# OpenBook_Schematic.net
KiCad netlist of a schematic drawn in EAGLE
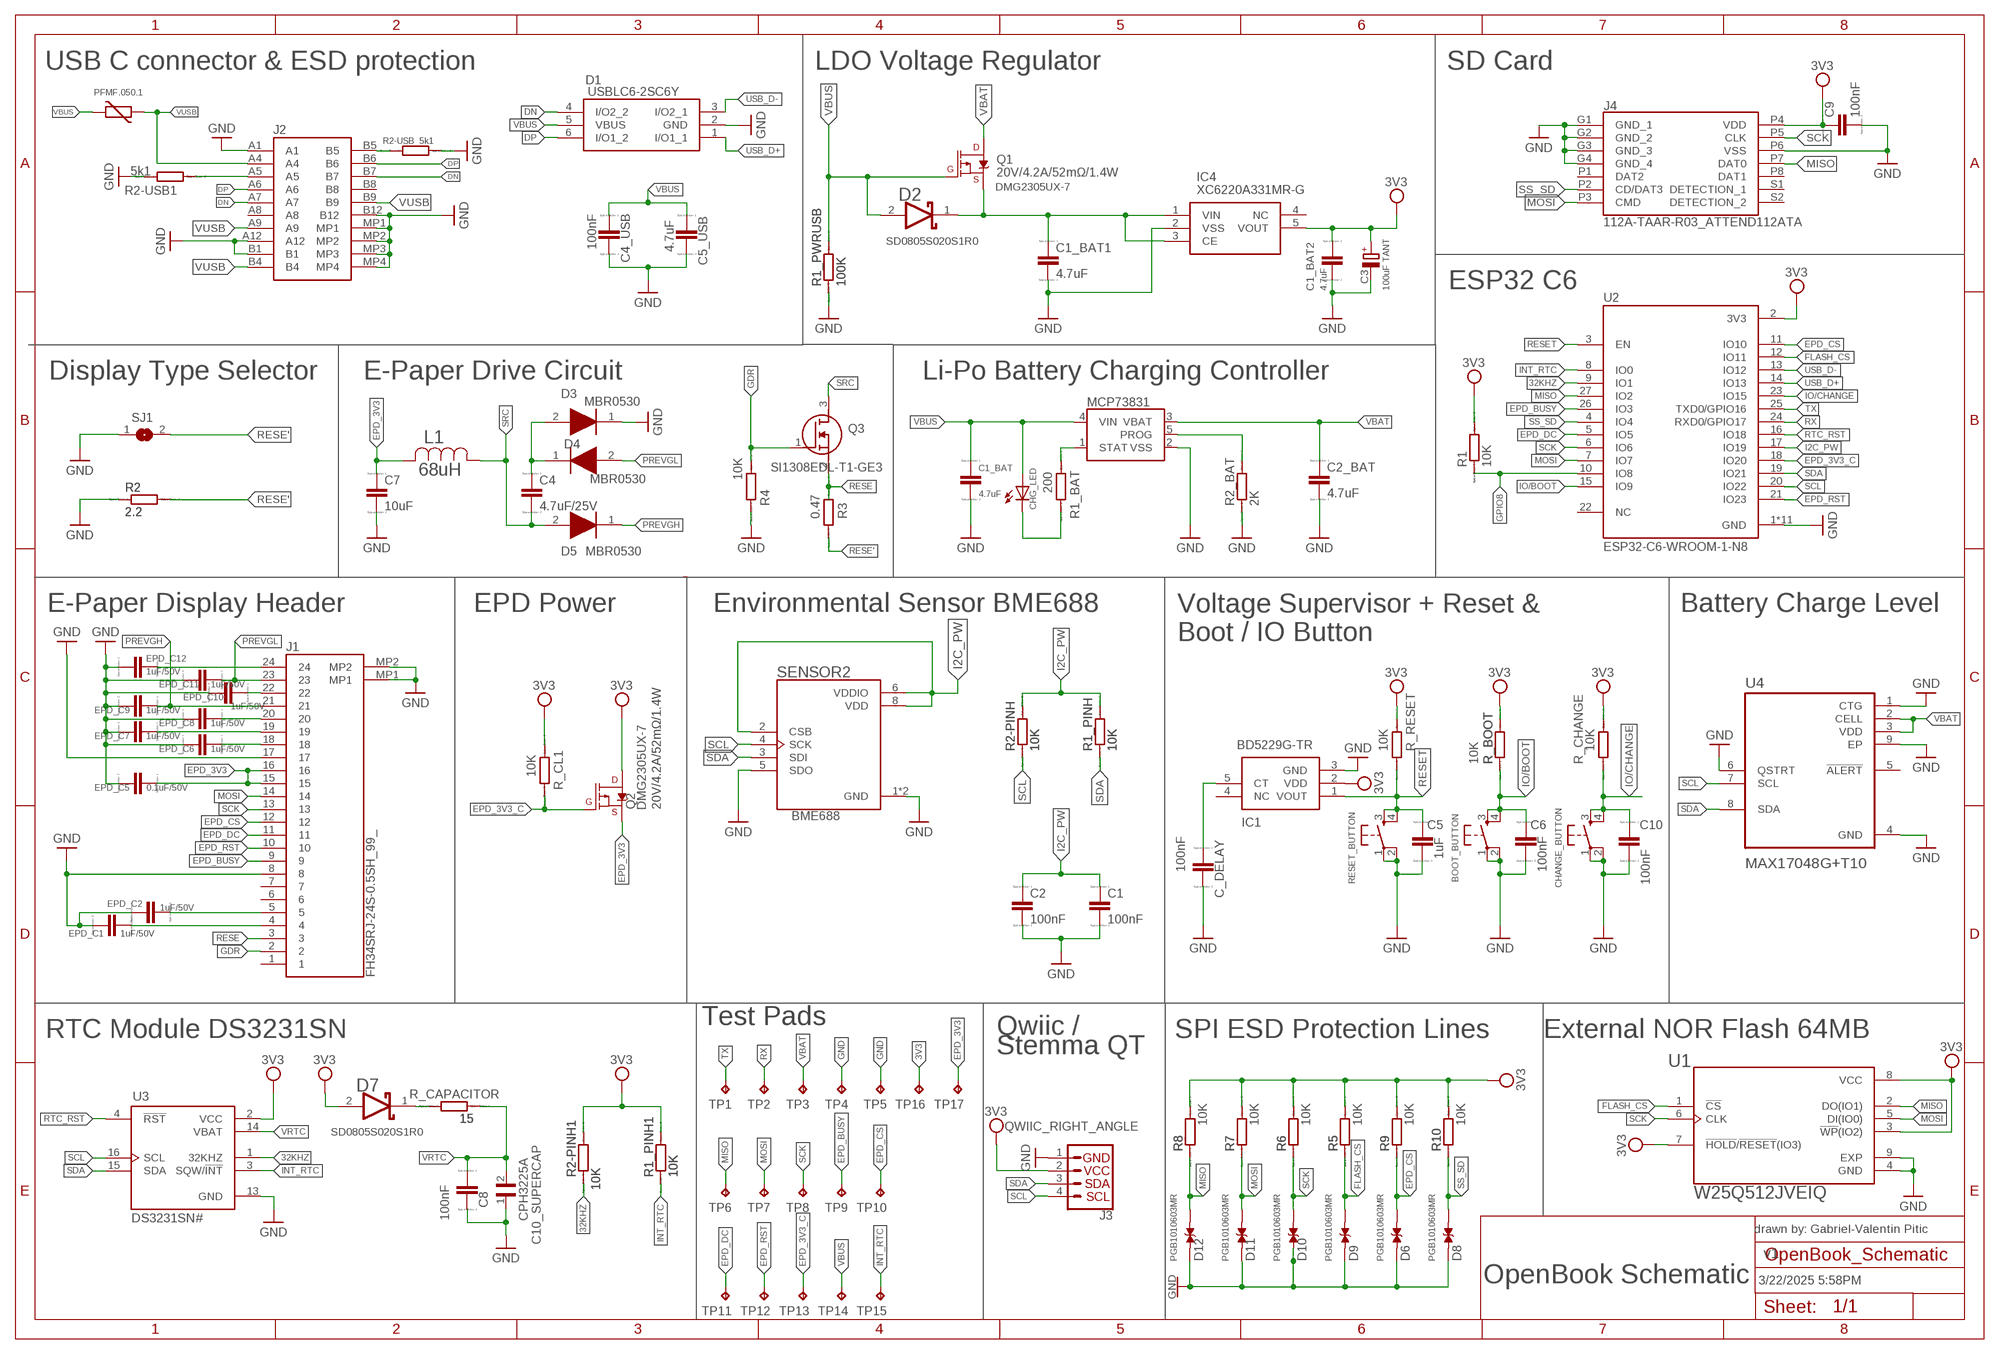
[diagram p0: schematic, sheet 1]

(export (version "E")
  (design (tool "Eeschema 10.0.6"))
  (components
    (comp (ref "BOOT_BUTTON")
      (value "BUTTON_CUSYOMV1")
      (footprint "eagle-import:MYBUTTON")
      (libsource (lib "eagle-import") (part "BUTTON_CUSYOMV1"))
    )
    (comp (ref "C1")
      (value "100nF")
      (footprint "eagle-import:ESP32_WROVER_EAGLE-LTSPICE_C0402")
      (libsource (lib "eagle-import") (part "EAGLE-LTSPICE_CC0402"))
    )
    (comp (ref "C1_BAT")
      (value "4.7uF")
      (footprint "eagle-import:ESP32_WROVER_EAGLE-LTSPICE_C0402")
      (libsource (lib "eagle-import") (part "EAGLE-LTSPICE_CC0402"))
    )
    (comp (ref "C1_BAT1")
      (value "4.7uF")
      (footprint "eagle-import:ESP32_WROVER_EAGLE-LTSPICE_C0402")
      (libsource (lib "eagle-import") (part "EAGLE-LTSPICE_CC0402"))
    )
    (comp (ref "C1_BAT2")
      (value "4.7uF")
      (footprint "eagle-import:ESP32_WROVER_EAGLE-LTSPICE_C0402")
      (libsource (lib "eagle-import") (part "EAGLE-LTSPICE_CC0402"))
    )
    (comp (ref "C2")
      (value "100nF")
      (footprint "eagle-import:ESP32_WROVER_EAGLE-LTSPICE_C0402")
      (libsource (lib "eagle-import") (part "EAGLE-LTSPICE_CC0402"))
    )
    (comp (ref "C2_BAT")
      (value "4.7uF")
      (footprint "eagle-import:ESP32_WROVER_EAGLE-LTSPICE_C0402")
      (libsource (lib "eagle-import") (part "EAGLE-LTSPICE_CC0402"))
    )
    (comp (ref "C3")
      (value "100uF TANT")
      (footprint "eagle-import:RCL_CT3528")
      (libsource (lib "eagle-import") (part "RCL_CPOL-EUCT3528"))
    )
    (comp (ref "C4")
      (value "4.7uF/25V")
      (footprint "eagle-import:ESP32_WROVER_EAGLE-LTSPICE_C0402")
      (libsource (lib "eagle-import") (part "EAGLE-LTSPICE_CC0402"))
    )
    (comp (ref "C4_USB")
      (value "100nF")
      (footprint "eagle-import:ESP32_WROVER_EAGLE-LTSPICE_C0402")
      (libsource (lib "eagle-import") (part "EAGLE-LTSPICE_CC0402"))
    )
    (comp (ref "C5")
      (value "1uF")
      (footprint "eagle-import:ESP32_WROVER_EAGLE-LTSPICE_C0402")
      (libsource (lib "eagle-import") (part "EAGLE-LTSPICE_CC0402"))
    )
    (comp (ref "C5_USB")
      (value "4.7uF")
      (footprint "eagle-import:ESP32_WROVER_EAGLE-LTSPICE_C0402")
      (libsource (lib "eagle-import") (part "EAGLE-LTSPICE_CC0402"))
    )
    (comp (ref "C6")
      (value "100nF")
      (footprint "eagle-import:ESP32_WROVER_EAGLE-LTSPICE_C0402")
      (libsource (lib "eagle-import") (part "EAGLE-LTSPICE_CC0402"))
    )
    (comp (ref "C7")
      (value "10uF")
      (footprint "eagle-import:ESP32_WROVER_EAGLE-LTSPICE_C0402")
      (libsource (lib "eagle-import") (part "EAGLE-LTSPICE_CC0402"))
    )
    (comp (ref "C8")
      (value "100nF")
      (footprint "eagle-import:ESP32_WROVER_EAGLE-LTSPICE_C0402")
      (libsource (lib "eagle-import") (part "EAGLE-LTSPICE_CC0402"))
    )
    (comp (ref "C9")
      (value "100nF")
      (footprint "eagle-import:ESP32_WROVER_EAGLE-LTSPICE_C0402")
      (libsource (lib "eagle-import") (part "EAGLE-LTSPICE_CC0402"))
    )
    (comp (ref "C10")
      (value "100nF")
      (footprint "eagle-import:ESP32_WROVER_EAGLE-LTSPICE_C0402")
      (libsource (lib "eagle-import") (part "EAGLE-LTSPICE_CC0402"))
    )
    (comp (ref "C10_SUPERCAP")
      (value "CPH3225A")
      (footprint "eagle-import:CAPCP3225X100N")
      (fields (field (name "MF") "Seiko Instruments"))
      (libsource (lib "eagle-import") (part "CPH3225A"))
    )
    (comp (ref "CHANGE_BUTTON")
      (value "BUTTON_CUSYOMV1")
      (footprint "eagle-import:MYBUTTON")
      (libsource (lib "eagle-import") (part "BUTTON_CUSYOMV1"))
    )
    (comp (ref "CHG_LED")
      (value "ADAFRUIT_LEDCHIP-LED0603")
      (footprint "eagle-import:ADAFRUIT_CHIP-LED0603")
      (libsource (lib "eagle-import") (part "ADAFRUIT_LEDCHIP-LED0603"))
    )
    (comp (ref "C_DELAY")
      (value "100nF")
      (footprint "eagle-import:ESP32_WROVER_EAGLE-LTSPICE_C0402")
      (libsource (lib "eagle-import") (part "EAGLE-LTSPICE_CC0402"))
    )
    (comp (ref "D1")
      (value "USBLC6-2SC6Y")
      (footprint "eagle-import:SOT95P280X145-6N")
      (fields (field (name "MF") "STMicroelectronics"))
      (libsource (lib "eagle-import") (part "USBLC6-2SC6Y"))
    )
    (comp (ref "D2")
      (value "ESP32_WROVER_AVX---SD0805S020S1R0_AVX_SD0805S020S1R0_0_0AVX_SD0805S020S1R0_0_0")
      (footprint "eagle-import:ESP32_WROVER_AVX---SD0805S020S1R0_AVX_SD0805S020S1R0_0")
      (fields
        (field (name "DIGIKEY_PART_NUMBER") "478-7800-1-ND")
        (field (name "MF") "AVX")
        (field (name "MOUSER_PART_NUMBER") "581-SD0805S020S1R0")
      )
      (libsource (lib "eagle-import") (part "ESP32_WROVER_AVX---SD0805S020S1R0_AVX_SD0805S020S1R0_0_0AVX_SD0805S020S1R0_0_0"))
    )
    (comp (ref "D3")
      (value "MBR0530")
      (footprint "eagle-import:SOD3716X135N")
      (fields (field (name "MF") "ON Semiconductor"))
      (libsource (lib "eagle-import") (part "MBR0530"))
    )
    (comp (ref "D4")
      (value "MBR0530")
      (footprint "eagle-import:SOD3716X135N")
      (fields (field (name "MF") "ON Semiconductor"))
      (libsource (lib "eagle-import") (part "MBR0530"))
    )
    (comp (ref "D5")
      (value "MBR0530")
      (footprint "eagle-import:SOD3716X135N")
      (fields (field (name "MF") "ON Semiconductor"))
      (libsource (lib "eagle-import") (part "MBR0530"))
    )
    (comp (ref "D6")
      (value "PGB1010603MR")
      (footprint "eagle-import:DIOC1608X36N")
      (fields (field (name "MF") "Littelfuse Inc."))
      (libsource (lib "eagle-import") (part "PGB1010603MR"))
    )
    (comp (ref "D7")
      (value "ESP32_WROVER_AVX---SD0805S020S1R0_AVX_SD0805S020S1R0_0_0AVX_SD0805S020S1R0_0_0")
      (footprint "eagle-import:ESP32_WROVER_AVX---SD0805S020S1R0_AVX_SD0805S020S1R0_0")
      (fields
        (field (name "DIGIKEY_PART_NUMBER") "478-7800-1-ND")
        (field (name "MF") "AVX")
        (field (name "MOUSER_PART_NUMBER") "581-SD0805S020S1R0")
      )
      (libsource (lib "eagle-import") (part "ESP32_WROVER_AVX---SD0805S020S1R0_AVX_SD0805S020S1R0_0_0AVX_SD0805S020S1R0_0_0"))
    )
    (comp (ref "D8")
      (value "PGB1010603MR")
      (footprint "eagle-import:DIOC1608X36N")
      (fields (field (name "MF") "Littelfuse Inc."))
      (libsource (lib "eagle-import") (part "PGB1010603MR"))
    )
    (comp (ref "D9")
      (value "PGB1010603MR")
      (footprint "eagle-import:DIOC1608X36N")
      (fields (field (name "MF") "Littelfuse Inc."))
      (libsource (lib "eagle-import") (part "PGB1010603MR"))
    )
    (comp (ref "D10")
      (value "PGB1010603MR")
      (footprint "eagle-import:DIOC1608X36N")
      (fields (field (name "MF") "Littelfuse Inc."))
      (libsource (lib "eagle-import") (part "PGB1010603MR"))
    )
    (comp (ref "D11")
      (value "PGB1010603MR")
      (footprint "eagle-import:DIOC1608X36N")
      (fields (field (name "MF") "Littelfuse Inc."))
      (libsource (lib "eagle-import") (part "PGB1010603MR"))
    )
    (comp (ref "D12")
      (value "PGB1010603MR")
      (footprint "eagle-import:DIOC1608X36N")
      (fields (field (name "MF") "Littelfuse Inc."))
      (libsource (lib "eagle-import") (part "PGB1010603MR"))
    )
    (comp (ref "EPD_C1")
      (value "1uF/50V")
      (footprint "eagle-import:ESP32_WROVER_EAGLE-LTSPICE_C0402")
      (libsource (lib "eagle-import") (part "EAGLE-LTSPICE_CC0402"))
    )
    (comp (ref "EPD_C2")
      (value "1uF/50V")
      (footprint "eagle-import:ESP32_WROVER_EAGLE-LTSPICE_C0402")
      (libsource (lib "eagle-import") (part "EAGLE-LTSPICE_CC0402"))
    )
    (comp (ref "EPD_C5")
      (value "0.1uF/50V")
      (footprint "eagle-import:ESP32_WROVER_EAGLE-LTSPICE_C0402")
      (libsource (lib "eagle-import") (part "EAGLE-LTSPICE_CC0402"))
    )
    (comp (ref "EPD_C6")
      (value "1uF/50V")
      (footprint "eagle-import:ESP32_WROVER_EAGLE-LTSPICE_C0402")
      (libsource (lib "eagle-import") (part "EAGLE-LTSPICE_CC0402"))
    )
    (comp (ref "EPD_C7")
      (value "1uF/50V")
      (footprint "eagle-import:ESP32_WROVER_EAGLE-LTSPICE_C0402")
      (libsource (lib "eagle-import") (part "EAGLE-LTSPICE_CC0402"))
    )
    (comp (ref "EPD_C8")
      (value "1uF/50V")
      (footprint "eagle-import:ESP32_WROVER_EAGLE-LTSPICE_C0402")
      (libsource (lib "eagle-import") (part "EAGLE-LTSPICE_CC0402"))
    )
    (comp (ref "EPD_C9")
      (value "1uF/50V")
      (footprint "eagle-import:ESP32_WROVER_EAGLE-LTSPICE_C0402")
      (libsource (lib "eagle-import") (part "EAGLE-LTSPICE_CC0402"))
    )
    (comp (ref "EPD_C10")
      (value "1uF/50V")
      (footprint "eagle-import:ESP32_WROVER_EAGLE-LTSPICE_C0402")
      (libsource (lib "eagle-import") (part "EAGLE-LTSPICE_CC0402"))
    )
    (comp (ref "EPD_C11")
      (value "1uF/50V")
      (footprint "eagle-import:ESP32_WROVER_EAGLE-LTSPICE_C0402")
      (libsource (lib "eagle-import") (part "EAGLE-LTSPICE_CC0402"))
    )
    (comp (ref "EPD_C12")
      (value "1uF/50V")
      (footprint "eagle-import:ESP32_WROVER_EAGLE-LTSPICE_C0402")
      (libsource (lib "eagle-import") (part "EAGLE-LTSPICE_CC0402"))
    )
    (comp (ref "IC1")
      (value "BD5229G-TR")
      (footprint "eagle-import:SOT95P280X125-5N")
      (fields (field (name "MOUSER_PART_NUMBER") "755-BD5229G-TR"))
      (libsource (lib "eagle-import") (part "BD5229G-TR"))
    )
    (comp (ref "IC4")
      (value "XC6220A331MR-G")
      (footprint "eagle-import:SOT95P280X120-5N")
      (fields (field (name "MOUSER_PART_NUMBER") "865-XC6220A331MR-G"))
      (libsource (lib "eagle-import") (part "XC6220A331MR-G"))
    )
    (comp (ref "J1")
      (value "FH34SRJ-24S-0.5SH_99_")
      (footprint "eagle-import:FH34SRJ24S05SH99")
      (fields
        (field (name "MANUFACTURER_PART_NUMBER") "FH34SRJ-24S-0.5SH(99)")
        (field (name "MOUSER_PART_NUMBER") "798-FH34SRJ24S05SH99")
      )
      (libsource (lib "eagle-import") (part "FH34SRJ-24S-0.5SH_99_"))
    )
    (comp (ref "J2")
      (value "SAMACSYS_PARTS_USB4110-GF-A")
      (footprint "eagle-import:SAMACSYS_PARTS_USB4110GFA")
      (libsource (lib "eagle-import") (part "SAMACSYS_PARTS_USB4110-GF-A"))
    )
    (comp (ref "J3")
      (value "QWIIC_RIGHT_ANGLE")
      (footprint "eagle-import:JST04_1MM_RA")
      (libsource (lib "eagle-import") (part "QWIIC_CONNECTORJS-1MM"))
    )
    (comp (ref "J4")
      (value "112A-TAAR-R03_ATTEND112ATA")
      (footprint "eagle-import:112ATAARR03ATTEND")
      (libsource (lib "eagle-import") (part "112A-TAAR-R03_ATTEND112ATA"))
    )
    (comp (ref "L1")
      (value "68uH")
      (footprint "eagle-import:IND_4828-WE-TPC_WRE")
      (fields
        (field (name "MANUFACTURER_PART_NUMBER") "744043680")
        (field (name "COPYRIGHT") "Copyright (C) 2024 Ultra Librarian. All rights reserved.")
      )
      (libsource (lib "eagle-import") (part "744043680IND_4828-WE-TPC_WRE"))
    )
    (comp (ref "MCP73831")
      (value "ESP32_WROVER_SPARKFUN-IC-POWER_MCP73831")
      (footprint "eagle-import:ESP32_WROVER_SPARKFUN-IC-POWER_SOT23-5")
      (libsource (lib "eagle-import") (part "ESP32_WROVER_SPARKFUN-IC-POWER_MCP73831"))
    )
    (comp (ref "PFMF.050.1")
      (value "ESP32C6_VARISTOR")
      (footprint "eagle-import:ESP32C6_VARISTOR_CT_CN1812")
      (libsource (lib "eagle-import") (part "ESP32C6_VARISTOR"))
    )
    (comp (ref "Q1")
      (value "20V/4.2A/52mΩ/1.4W")
      (footprint "eagle-import:ESP32_WROVER_SPARKFUN-DISCRETESEMI_SOT23-3")
      (libsource (lib "eagle-import") (part "ESP32_WROVER_SPARKFUN-DISCRETESEMI_MOSFET_PCH-DMG2305UX-7"))
    )
    (comp (ref "Q2")
      (value "20V/4.2A/52mΩ/1.4W")
      (footprint "eagle-import:ESP32_WROVER_SPARKFUN-DISCRETESEMI_SOT23-3")
      (libsource (lib "eagle-import") (part "ESP32_WROVER_SPARKFUN-DISCRETESEMI_MOSFET_PCH-DMG2305UX-7"))
    )
    (comp (ref "Q3")
      (value "SI1308EDL-T1-GE3")
      (footprint "eagle-import:SOT65P210X110-3N")
      (fields (field (name "MF") "Vishay Siliconix"))
      (libsource (lib "eagle-import") (part "SI1308EDL-T1-GE3"))
    )
    (comp (ref "R1")
      (value "10K")
      (footprint "eagle-import:ESP32_WROVER_EAGLE-LTSPICE_R0402")
      (libsource (lib "eagle-import") (part "ESP32_WROVER_EAGLE-LTSPICE_RR0402"))
    )
    (comp (ref "R1_BAT")
      (value "200")
      (footprint "eagle-import:ESP32_WROVER_EAGLE-LTSPICE_R0402")
      (libsource (lib "eagle-import") (part "ESP32_WROVER_EAGLE-LTSPICE_RR0402"))
    )
    (comp (ref "R1_PINH")
      (value "10K")
      (footprint "eagle-import:ESP32_WROVER_EAGLE-LTSPICE_R0402")
      (libsource (lib "eagle-import") (part "ESP32_WROVER_EAGLE-LTSPICE_RR0402"))
    )
    (comp (ref "R1_PINH1")
      (value "10K")
      (footprint "eagle-import:ESP32_WROVER_EAGLE-LTSPICE_R0402")
      (libsource (lib "eagle-import") (part "ESP32_WROVER_EAGLE-LTSPICE_RR0402"))
    )
    (comp (ref "R1_PWRUSB")
      (value "100K")
      (footprint "eagle-import:ESP32_WROVER_EAGLE-LTSPICE_R0402")
      (libsource (lib "eagle-import") (part "ESP32_WROVER_EAGLE-LTSPICE_RR0402"))
    )
    (comp (ref "R2")
      (value "2.2")
      (footprint "eagle-import:ESP32_WROVER_EAGLE-LTSPICE_R0402")
      (libsource (lib "eagle-import") (part "ESP32_WROVER_EAGLE-LTSPICE_RR0402"))
    )
    (comp (ref "R2-PINH")
      (value "10K")
      (footprint "eagle-import:ESP32_WROVER_EAGLE-LTSPICE_R0402")
      (libsource (lib "eagle-import") (part "ESP32_WROVER_EAGLE-LTSPICE_RR0402"))
    )
    (comp (ref "R2-PINH1")
      (value "10K")
      (footprint "eagle-import:ESP32_WROVER_EAGLE-LTSPICE_R0402")
      (libsource (lib "eagle-import") (part "ESP32_WROVER_EAGLE-LTSPICE_RR0402"))
    )
    (comp (ref "R2-USB")
      (value "5k1")
      (footprint "eagle-import:ESP32_WROVER_EAGLE-LTSPICE_R0402")
      (libsource (lib "eagle-import") (part "ESP32_WROVER_EAGLE-LTSPICE_RR0402"))
    )
    (comp (ref "R2-USB1")
      (value "5k1")
      (footprint "eagle-import:ESP32_WROVER_EAGLE-LTSPICE_R0402")
      (libsource (lib "eagle-import") (part "ESP32_WROVER_EAGLE-LTSPICE_RR0402"))
    )
    (comp (ref "R2_BAT")
      (value "2K")
      (footprint "eagle-import:ESP32_WROVER_EAGLE-LTSPICE_R0402")
      (libsource (lib "eagle-import") (part "ESP32_WROVER_EAGLE-LTSPICE_RR0402"))
    )
    (comp (ref "R3")
      (value "0.47")
      (footprint "eagle-import:ESP32_WROVER_EAGLE-LTSPICE_R0402")
      (libsource (lib "eagle-import") (part "ESP32_WROVER_EAGLE-LTSPICE_RR0402"))
    )
    (comp (ref "R4")
      (value "10K")
      (footprint "eagle-import:ESP32_WROVER_EAGLE-LTSPICE_R0402")
      (libsource (lib "eagle-import") (part "ESP32_WROVER_EAGLE-LTSPICE_RR0402"))
    )
    (comp (ref "R5")
      (value "10K")
      (footprint "eagle-import:ESP32_WROVER_EAGLE-LTSPICE_R0402")
      (libsource (lib "eagle-import") (part "ESP32_WROVER_EAGLE-LTSPICE_RR0402"))
    )
    (comp (ref "R6")
      (value "10K")
      (footprint "eagle-import:ESP32_WROVER_EAGLE-LTSPICE_R0402")
      (libsource (lib "eagle-import") (part "ESP32_WROVER_EAGLE-LTSPICE_RR0402"))
    )
    (comp (ref "R7")
      (value "10K")
      (footprint "eagle-import:ESP32_WROVER_EAGLE-LTSPICE_R0402")
      (libsource (lib "eagle-import") (part "ESP32_WROVER_EAGLE-LTSPICE_RR0402"))
    )
    (comp (ref "R8")
      (value "10K")
      (footprint "eagle-import:ESP32_WROVER_EAGLE-LTSPICE_R0402")
      (libsource (lib "eagle-import") (part "ESP32_WROVER_EAGLE-LTSPICE_RR0402"))
    )
    (comp (ref "R9")
      (value "10K")
      (footprint "eagle-import:ESP32_WROVER_EAGLE-LTSPICE_R0402")
      (libsource (lib "eagle-import") (part "ESP32_WROVER_EAGLE-LTSPICE_RR0402"))
    )
    (comp (ref "R10")
      (value "10K")
      (footprint "eagle-import:ESP32_WROVER_EAGLE-LTSPICE_R0402")
      (libsource (lib "eagle-import") (part "ESP32_WROVER_EAGLE-LTSPICE_RR0402"))
    )
    (comp (ref "RESET_BUTTON")
      (value "BUTTON_CUSYOMV1")
      (footprint "eagle-import:MYBUTTON")
      (libsource (lib "eagle-import") (part "BUTTON_CUSYOMV1"))
    )
    (comp (ref "R_BOOT")
      (value "10K")
      (footprint "eagle-import:ESP32_WROVER_EAGLE-LTSPICE_R0402")
      (libsource (lib "eagle-import") (part "ESP32_WROVER_EAGLE-LTSPICE_RR0402"))
    )
    (comp (ref "R_CAPACITOR")
      (value "15")
      (footprint "eagle-import:ESP32_WROVER_EAGLE-LTSPICE_R0402")
      (libsource (lib "eagle-import") (part "ESP32_WROVER_EAGLE-LTSPICE_RR0402"))
    )
    (comp (ref "R_CHANGE")
      (value "10K")
      (footprint "eagle-import:ESP32_WROVER_EAGLE-LTSPICE_R0402")
      (libsource (lib "eagle-import") (part "ESP32_WROVER_EAGLE-LTSPICE_RR0402"))
    )
    (comp (ref "R_CL1")
      (value "10K")
      (footprint "eagle-import:ESP32_WROVER_EAGLE-LTSPICE_R0402")
      (libsource (lib "eagle-import") (part "ESP32_WROVER_EAGLE-LTSPICE_RR0402"))
    )
    (comp (ref "R_RESET")
      (value "10K")
      (footprint "eagle-import:ESP32_WROVER_EAGLE-LTSPICE_R0402")
      (libsource (lib "eagle-import") (part "ESP32_WROVER_EAGLE-LTSPICE_RR0402"))
    )
    (comp (ref "SENSOR2")
      (value "ESP32_WROVER_BME680_BME680")
      (footprint "eagle-import:ESP32_WROVER_BME680_PSON80P300X300X100-8N")
      (fields (field (name "MF") "Bosch Sensortec") (field (name "MP") "BME680"))
      (libsource (lib "eagle-import") (part "ESP32_WROVER_BME680_BME680"))
    )
    (comp (ref "SJ1") (value "SJ") (footprint "eagle-import:SJ") (libsource (lib "eagle-import") (part "SJ")))
    (comp (ref "TP1")
      (value "TPTP20R")
      (footprint "eagle-import:TP20R")
      (libsource (lib "eagle-import") (part "TPTP20R"))
    )
    (comp (ref "TP2")
      (value "TPTP20R")
      (footprint "eagle-import:TP20R")
      (libsource (lib "eagle-import") (part "TPTP20R"))
    )
    (comp (ref "TP3")
      (value "TPTP20R")
      (footprint "eagle-import:TP20R")
      (libsource (lib "eagle-import") (part "TPTP20R"))
    )
    (comp (ref "TP4")
      (value "TPTP20R")
      (footprint "eagle-import:TP20R")
      (libsource (lib "eagle-import") (part "TPTP20R"))
    )
    (comp (ref "TP5")
      (value "TPTP20R")
      (footprint "eagle-import:TP20R")
      (libsource (lib "eagle-import") (part "TPTP20R"))
    )
    (comp (ref "TP6")
      (value "TPTP20R")
      (footprint "eagle-import:TP20R")
      (libsource (lib "eagle-import") (part "TPTP20R"))
    )
    (comp (ref "TP7")
      (value "TPTP20R")
      (footprint "eagle-import:TP20R")
      (libsource (lib "eagle-import") (part "TPTP20R"))
    )
    (comp (ref "TP8")
      (value "TPTP20R")
      (footprint "eagle-import:TP20R")
      (libsource (lib "eagle-import") (part "TPTP20R"))
    )
    (comp (ref "TP9")
      (value "TPTP20R")
      (footprint "eagle-import:TP20R")
      (libsource (lib "eagle-import") (part "TPTP20R"))
    )
    (comp (ref "TP10")
      (value "TPTP20R")
      (footprint "eagle-import:TP20R")
      (libsource (lib "eagle-import") (part "TPTP20R"))
    )
    (comp (ref "TP11")
      (value "TPTP20R")
      (footprint "eagle-import:TP20R")
      (libsource (lib "eagle-import") (part "TPTP20R"))
    )
    (comp (ref "TP12")
      (value "TPTP20R")
      (footprint "eagle-import:TP20R")
      (libsource (lib "eagle-import") (part "TPTP20R"))
    )
    (comp (ref "TP13")
      (value "TPTP20R")
      (footprint "eagle-import:TP20R")
      (libsource (lib "eagle-import") (part "TPTP20R"))
    )
    (comp (ref "TP14")
      (value "TPTP20R")
      (footprint "eagle-import:TP20R")
      (libsource (lib "eagle-import") (part "TPTP20R"))
    )
    (comp (ref "TP15")
      (value "TPTP20R")
      (footprint "eagle-import:TP20R")
      (libsource (lib "eagle-import") (part "TPTP20R"))
    )
    (comp (ref "TP16")
      (value "TPTP20R")
      (footprint "eagle-import:TP20R")
      (libsource (lib "eagle-import") (part "TPTP20R"))
    )
    (comp (ref "TP17")
      (value "TPTP20R")
      (footprint "eagle-import:TP20R")
      (libsource (lib "eagle-import") (part "TPTP20R"))
    )
    (comp (ref "U1")
      (value "W25Q512JVEIQ")
      (footprint "eagle-import:SON50P200X200X80-9N")
      (fields (field (name "MF") "Winbond Electronics"))
      (libsource (lib "eagle-import") (part "W25Q512JVEIQ"))
    )
    (comp (ref "U2")
      (value "ESP32-C6-WROOM-1-N8")
      (footprint "eagle-import:ESP32-C6-WROOM-1-N8")
      (libsource (lib "eagle-import") (part "ESP32-C6-WROOM-1-N8"))
    )
    (comp (ref "U3")
      (value "DS3231SN#")
      (footprint "eagle-import:SOIC127P1032X265-16N")
      (fields (field (name "MF") "Analog Devices"))
      (libsource (lib "eagle-import") (part "DS3231SN#"))
    )
    (comp (ref "U4")
      (value "MAX17048G+T10")
      (footprint "eagle-import:SON50P200X200X80-9N")
      (fields (field (name "MF") "Analog Devices"))
      (libsource (lib "eagle-import") (part "MAX17048G+T10"))
    )
  )
  (nets
    (net (code "1") (name "/CHG_STATUS") (class "Default")
      (node (ref "CHG_LED") (pin "C") (pinfunction "C_C") (pintype "passive"))
      (node (ref "MCP73831") (pin "1") (pinfunction "STAT_1") (pintype "output"))
      (node (ref "R1_BAT") (pin "1") (pinfunction "1_1") (pintype "passive"))
      (node (ref "R1_BAT") (pin "2") (pinfunction "2_2") (pintype "passive"))
    )
    (net (code "2") (name "3V3") (class "Default")
      (node (ref "C1_BAT2") (pin "1") (pinfunction "1_1") (pintype "passive"))
      (node (ref "C3") (pin "+") (pinfunction "+_+") (pintype "passive"))
      (node (ref "C9") (pin "1") (pinfunction "1_1") (pintype "passive"))
      (node (ref "D7") (pin "2") (pinfunction "ANODE_2") (pintype "bidirectional"))
      (node (ref "IC1") (pin "2") (pinfunction "VDD_2") (pintype "bidirectional"))
      (node (ref "IC4") (pin "5") (pinfunction "VOUT_5") (pintype "bidirectional"))
      (node (ref "J3") (pin "2") (pinfunction "2_2") (pintype "power_in"))
      (node (ref "J4") (pin "P4") (pinfunction "VDD_P4") (pintype "bidirectional"))
      (node (ref "Q2") (pin "3") (pinfunction "D_3") (pintype "bidirectional"))
      (node (ref "R1") (pin "2") (pinfunction "2_2") (pintype "passive"))
      (node (ref "R10") (pin "2") (pinfunction "2_2") (pintype "passive"))
      (node (ref "R1_PINH1") (pin "2") (pinfunction "2_2") (pintype "passive"))
      (node (ref "R2-PINH1") (pin "2") (pinfunction "2_2") (pintype "passive"))
      (node (ref "R5") (pin "2") (pinfunction "2_2") (pintype "passive"))
      (node (ref "R6") (pin "2") (pinfunction "2_2") (pintype "passive"))
      (node (ref "R7") (pin "2") (pinfunction "2_2") (pintype "passive"))
      (node (ref "R8") (pin "2") (pinfunction "2_2") (pintype "passive"))
      (node (ref "R9") (pin "2") (pinfunction "2_2") (pintype "passive"))
      (node (ref "R_BOOT") (pin "2") (pinfunction "2_2") (pintype "passive"))
      (node (ref "R_CHANGE") (pin "2") (pinfunction "2_2") (pintype "passive"))
      (node (ref "R_CL1") (pin "2") (pinfunction "2_2") (pintype "passive"))
      (node (ref "R_RESET") (pin "2") (pinfunction "2_2") (pintype "passive"))
      (node (ref "TP16") (pin "TP") (pinfunction "TP_TP") (pintype "input"))
      (node (ref "U1") (pin "3") (pinfunction "~{WP}(IO2)_3") (pintype "bidirectional"))
      (node (ref "U1") (pin "7") (pinfunction "~{HOLD}/~{RESET}(IO3)_7") (pintype "bidirectional"))
      (node (ref "U1") (pin "8") (pinfunction "VCC_8") (pintype "power_in"))
      (node (ref "U2") (pin "2") (pinfunction "3V3_2") (pintype "power_in"))
      (node (ref "U3") (pin "2") (pinfunction "VCC_2") (pintype "power_in"))
    )
    (net (code "3") (name "32KHZ") (class "Default")
      (node (ref "R2-PINH1") (pin "1") (pinfunction "1_1") (pintype "passive"))
      (node (ref "U2") (pin "9") (pinfunction "IO1_9") (pintype "bidirectional"))
      (node (ref "U3") (pin "1") (pinfunction "32KHZ_1") (pintype "output"))
    )
    (net (code "4") (name "DN") (class "Default")
      (node (ref "D1") (pin "4") (pinfunction "I/O2_2_4") (pintype "bidirectional"))
      (node (ref "J2") (pin "A7") (pinfunction "A7_A7") (pintype "bidirectional"))
      (node (ref "J2") (pin "B7") (pinfunction "B7_B7") (pintype "bidirectional"))
    )
    (net (code "5") (name "DP") (class "Default")
      (node (ref "D1") (pin "6") (pinfunction "I/O1_2_6") (pintype "bidirectional"))
      (node (ref "J2") (pin "A6") (pinfunction "A6_A6") (pintype "bidirectional"))
      (node (ref "J2") (pin "B6") (pinfunction "B6_B6") (pintype "bidirectional"))
    )
    (net (code "6") (name "EPD_3V3") (class "Default")
      (node (ref "C7") (pin "1") (pinfunction "1_1") (pintype "passive"))
      (node (ref "EPD_C5") (pin "1") (pinfunction "1_1") (pintype "passive"))
      (node (ref "J1") (pin "15") (pinfunction "15_15") (pintype "bidirectional"))
      (node (ref "J1") (pin "16") (pinfunction "16_16") (pintype "bidirectional"))
      (node (ref "L1") (pin "2") (pinfunction "2_2") (pintype "passive"))
      (node (ref "Q2") (pin "2") (pinfunction "S_2") (pintype "bidirectional"))
      (node (ref "TP17") (pin "TP") (pinfunction "TP_TP") (pintype "input"))
    )
    (net (code "7") (name "EPD_3V3_C") (class "Default")
      (node (ref "Q2") (pin "1") (pinfunction "G_1") (pintype "bidirectional"))
      (node (ref "R_CL1") (pin "1") (pinfunction "1_1") (pintype "passive"))
      (node (ref "TP13") (pin "TP") (pinfunction "TP_TP") (pintype "input"))
      (node (ref "U2") (pin "18") (pinfunction "IO20_18") (pintype "bidirectional"))
    )
    (net (code "8") (name "EPD_BUSY") (class "Default")
      (node (ref "J1") (pin "9") (pinfunction "9_9") (pintype "bidirectional"))
      (node (ref "TP9") (pin "TP") (pinfunction "TP_TP") (pintype "input"))
      (node (ref "U2") (pin "26") (pinfunction "IO3_26") (pintype "bidirectional"))
    )
    (net (code "9") (name "EPD_CS") (class "Default")
      (node (ref "D6") (pin "2") (pinfunction "2_2") (pintype "passive"))
      (node (ref "J1") (pin "12") (pinfunction "12_12") (pintype "bidirectional"))
      (node (ref "R9") (pin "1") (pinfunction "1_1") (pintype "passive"))
      (node (ref "TP10") (pin "TP") (pinfunction "TP_TP") (pintype "input"))
      (node (ref "U2") (pin "11") (pinfunction "IO10_11") (pintype "bidirectional"))
    )
    (net (code "10") (name "EPD_DC") (class "Default")
      (node (ref "J1") (pin "11") (pinfunction "11_11") (pintype "bidirectional"))
      (node (ref "TP11") (pin "TP") (pinfunction "TP_TP") (pintype "input"))
      (node (ref "U2") (pin "5") (pinfunction "IO5_5") (pintype "bidirectional"))
    )
    (net (code "11") (name "EPD_RST") (class "Default")
      (node (ref "J1") (pin "10") (pinfunction "10_10") (pintype "bidirectional"))
      (node (ref "TP12") (pin "TP") (pinfunction "TP_TP") (pintype "input"))
      (node (ref "U2") (pin "21") (pinfunction "IO23_21") (pintype "bidirectional"))
    )
    (net (code "12") (name "FLASH_CS") (class "Default")
      (node (ref "D9") (pin "2") (pinfunction "2_2") (pintype "passive"))
      (node (ref "R5") (pin "1") (pinfunction "1_1") (pintype "passive"))
      (node (ref "U1") (pin "1") (pinfunction "~{CS}_1") (pintype "input"))
      (node (ref "U2") (pin "12") (pinfunction "IO11_12") (pintype "bidirectional"))
    )
    (net (code "13") (name "GDR") (class "Default")
      (node (ref "J1") (pin "2") (pinfunction "2_2") (pintype "bidirectional"))
      (node (ref "Q3") (pin "1") (pinfunction "G_1") (pintype "bidirectional"))
      (node (ref "R4") (pin "2") (pinfunction "2_2") (pintype "passive"))
    )
    (net (code "14") (name "GND") (class "Default")
      (node (ref "BOOT_BUTTON") (pin "1") (pinfunction "1_1") (pintype "passive"))
      (node (ref "BOOT_BUTTON") (pin "2") (pinfunction "2_2") (pintype "passive"))
      (node (ref "C1") (pin "2") (pinfunction "2_2") (pintype "passive"))
      (node (ref "C10") (pin "2") (pinfunction "2_2") (pintype "passive"))
      (node (ref "C10_SUPERCAP") (pin "1") (pinfunction "1_1") (pintype "passive"))
      (node (ref "C1_BAT") (pin "2") (pinfunction "2_2") (pintype "passive"))
      (node (ref "C1_BAT1") (pin "2") (pinfunction "2_2") (pintype "passive"))
      (node (ref "C1_BAT2") (pin "2") (pinfunction "2_2") (pintype "passive"))
      (node (ref "C2") (pin "2") (pinfunction "2_2") (pintype "passive"))
      (node (ref "C2_BAT") (pin "2") (pinfunction "2_2") (pintype "passive"))
      (node (ref "C3") (pin "-") (pinfunction "-_-") (pintype "passive"))
      (node (ref "C4_USB") (pin "2") (pinfunction "2_2") (pintype "passive"))
      (node (ref "C5") (pin "2") (pinfunction "2_2") (pintype "passive"))
      (node (ref "C5_USB") (pin "2") (pinfunction "2_2") (pintype "passive"))
      (node (ref "C6") (pin "2") (pinfunction "2_2") (pintype "passive"))
      (node (ref "C7") (pin "2") (pinfunction "2_2") (pintype "passive"))
      (node (ref "C8") (pin "2") (pinfunction "2_2") (pintype "passive"))
      (node (ref "C9") (pin "2") (pinfunction "2_2") (pintype "passive"))
      (node (ref "CHANGE_BUTTON") (pin "1") (pinfunction "1_1") (pintype "passive"))
      (node (ref "CHANGE_BUTTON") (pin "2") (pinfunction "2_2") (pintype "passive"))
      (node (ref "C_DELAY") (pin "2") (pinfunction "2_2") (pintype "passive"))
      (node (ref "D1") (pin "2") (pinfunction "GND_2") (pintype "bidirectional"))
      (node (ref "D10") (pin "1") (pinfunction "1_1") (pintype "passive"))
      (node (ref "D11") (pin "1") (pinfunction "1_1") (pintype "passive"))
      (node (ref "D12") (pin "1") (pinfunction "1_1") (pintype "passive"))
      (node (ref "D3") (pin "1") (pinfunction "K_1") (pintype "bidirectional"))
      (node (ref "D6") (pin "1") (pinfunction "1_1") (pintype "passive"))
      (node (ref "D8") (pin "1") (pinfunction "1_1") (pintype "passive"))
      (node (ref "D9") (pin "1") (pinfunction "1_1") (pintype "passive"))
      (node (ref "EPD_C1") (pin "2") (pinfunction "2_2") (pintype "passive"))
      (node (ref "EPD_C10") (pin "2") (pinfunction "2_2") (pintype "passive"))
      (node (ref "EPD_C11") (pin "2") (pinfunction "2_2") (pintype "passive"))
      (node (ref "EPD_C12") (pin "2") (pinfunction "2_2") (pintype "passive"))
      (node (ref "EPD_C2") (pin "1") (pinfunction "1_1") (pintype "passive"))
      (node (ref "EPD_C5") (pin "2") (pinfunction "2_2") (pintype "passive"))
      (node (ref "EPD_C6") (pin "2") (pinfunction "2_2") (pintype "passive"))
      (node (ref "EPD_C7") (pin "2") (pinfunction "2_2") (pintype "passive"))
      (node (ref "EPD_C8") (pin "2") (pinfunction "2_2") (pintype "passive"))
      (node (ref "EPD_C9") (pin "2") (pinfunction "2_2") (pintype "passive"))
      (node (ref "IC1") (pin "3") (pinfunction "GND_3") (pintype "bidirectional"))
      (node (ref "IC4") (pin "2") (pinfunction "VSS_2") (pintype "bidirectional"))
      (node (ref "J1") (pin "17") (pinfunction "17_17") (pintype "bidirectional"))
      (node (ref "J1") (pin "8") (pinfunction "8_8") (pintype "bidirectional"))
      (node (ref "J1") (pin "MP1") (pinfunction "MP1_MP1") (pintype "bidirectional"))
      (node (ref "J1") (pin "MP2") (pinfunction "MP2_MP2") (pintype "bidirectional"))
      (node (ref "J2") (pin "A1") (pinfunction "A1_A1") (pintype "bidirectional"))
      (node (ref "J2") (pin "A12") (pinfunction "A12_A12") (pintype "bidirectional"))
      (node (ref "J2") (pin "B1") (pinfunction "B1_B1") (pintype "bidirectional"))
      (node (ref "J2") (pin "B12") (pinfunction "B12_B12") (pintype "bidirectional"))
      (node (ref "J2") (pin "MP1") (pinfunction "MP1_MP1") (pintype "bidirectional"))
      (node (ref "J2") (pin "MP2") (pinfunction "MP2_MP2") (pintype "bidirectional"))
      (node (ref "J2") (pin "MP3") (pinfunction "MP3_MP3") (pintype "bidirectional"))
      (node (ref "J2") (pin "MP4") (pinfunction "MP4_MP4") (pintype "bidirectional"))
      (node (ref "J3") (pin "1") (pinfunction "1_1") (pintype "power_in"))
      (node (ref "J4") (pin "G1") (pinfunction "GND_1_G1") (pintype "bidirectional"))
      (node (ref "J4") (pin "G2") (pinfunction "GND_2_G2") (pintype "bidirectional"))
      (node (ref "J4") (pin "G3") (pinfunction "GND_3_G3") (pintype "bidirectional"))
      (node (ref "J4") (pin "G4") (pinfunction "GND_4_G4") (pintype "bidirectional"))
      (node (ref "J4") (pin "P6") (pinfunction "VSS_P6") (pintype "bidirectional"))
      (node (ref "MCP73831") (pin "2") (pinfunction "VSS_2") (pintype "power_in"))
      (node (ref "R1_PWRUSB") (pin "1") (pinfunction "1_1") (pintype "passive"))
      (node (ref "R2") (pin "1") (pinfunction "1_1") (pintype "passive"))
      (node (ref "R2-USB") (pin "2") (pinfunction "2_2") (pintype "passive"))
      (node (ref "R2-USB1") (pin "1") (pinfunction "1_1") (pintype "passive"))
      (node (ref "R2_BAT") (pin "1") (pinfunction "1_1") (pintype "passive"))
      (node (ref "R4") (pin "1") (pinfunction "1_1") (pintype "passive"))
      (node (ref "RESET_BUTTON") (pin "1") (pinfunction "1_1") (pintype "passive"))
      (node (ref "RESET_BUTTON") (pin "2") (pinfunction "2_2") (pintype "passive"))
      (node (ref "SENSOR2") (pin "1") (pinfunction "GND_1") (pintype "power_in"))
      (node (ref "SENSOR2") (pin "5") (pinfunction "SDO_5") (pintype "bidirectional"))
      (node (ref "SENSOR2") (pin "7") (pinfunction "GND_7") (pintype "power_in"))
      (node (ref "SJ1") (pin "1") (pinfunction "1_1") (pintype "passive"))
      (node (ref "TP4") (pin "TP") (pinfunction "TP_TP") (pintype "input"))
      (node (ref "TP5") (pin "TP") (pinfunction "TP_TP") (pintype "input"))
      (node (ref "U1") (pin "4") (pinfunction "GND_4") (pintype "power_in"))
      (node (ref "U1") (pin "9") (pinfunction "EXP_9") (pintype "passive"))
      (node (ref "U2") (pin "1") (pinfunction "GND_1") (pintype "power_in"))
      (node (ref "U2") (pin "28") (pinfunction "GND_28") (pintype "power_in"))
      (node (ref "U2") (pin "29_1") (pinfunction "GND_29_1") (pintype "power_in"))
      (node (ref "U2") (pin "29_2") (pinfunction "GND_29_2") (pintype "power_in"))
      (node (ref "U2") (pin "29_3") (pinfunction "GND_29_3") (pintype "power_in"))
      (node (ref "U2") (pin "29_4") (pinfunction "GND_29_4") (pintype "power_in"))
      (node (ref "U2") (pin "29_5") (pinfunction "GND_29_5") (pintype "power_in"))
      (node (ref "U2") (pin "29_6") (pinfunction "GND_29_6") (pintype "power_in"))
      (node (ref "U2") (pin "29_7") (pinfunction "GND_29_7") (pintype "power_in"))
      (node (ref "U2") (pin "29_8") (pinfunction "GND_29_8") (pintype "power_in"))
      (node (ref "U2") (pin "29_9") (pinfunction "GND_29_9") (pintype "power_in"))
      (node (ref "U3") (pin "13") (pinfunction "GND_13") (pintype "power_in"))
      (node (ref "U4") (pin "1") (pinfunction "CTG_1") (pintype "power_in"))
      (node (ref "U4") (pin "4") (pinfunction "GND_4") (pintype "power_in"))
      (node (ref "U4") (pin "6") (pinfunction "QSTRT_6") (pintype "input"))
      (node (ref "U4") (pin "9") (pinfunction "EP_9") (pintype "power_in"))
    )
    (net (code "15") (name "GPIO8") (class "Default")
      (node (ref "R1") (pin "1") (pinfunction "1_1") (pintype "passive"))
      (node (ref "U2") (pin "10") (pinfunction "IO8_10") (pintype "bidirectional"))
    )
    (net (code "16") (name "I2C_PW") (class "Default")
      (node (ref "C1") (pin "1") (pinfunction "1_1") (pintype "passive"))
      (node (ref "C2") (pin "1") (pinfunction "1_1") (pintype "passive"))
      (node (ref "R1_PINH") (pin "2") (pinfunction "2_2") (pintype "passive"))
      (node (ref "R2-PINH") (pin "2") (pinfunction "2_2") (pintype "passive"))
      (node (ref "SENSOR2") (pin "2") (pinfunction "CSB_2") (pintype "input"))
      (node (ref "SENSOR2") (pin "6") (pinfunction "VDDIO_6") (pintype "power_in"))
      (node (ref "SENSOR2") (pin "8") (pinfunction "VDD_8") (pintype "power_in"))
      (node (ref "U2") (pin "17") (pinfunction "IO19_17") (pintype "bidirectional"))
    )
    (net (code "17") (name "INT_RTC") (class "Default")
      (node (ref "R1_PINH1") (pin "1") (pinfunction "1_1") (pintype "passive"))
      (node (ref "TP15") (pin "TP") (pinfunction "TP_TP") (pintype "input"))
      (node (ref "U2") (pin "8") (pinfunction "IO0_8") (pintype "bidirectional"))
      (node (ref "U3") (pin "3") (pinfunction "SQW/~{INT}_3") (pintype "output"))
    )
    (net (code "18") (name "IO{slash}BOOT") (class "Default")
      (node (ref "BOOT_BUTTON") (pin "3") (pinfunction "3_3") (pintype "passive"))
      (node (ref "BOOT_BUTTON") (pin "4") (pinfunction "4_4") (pintype "passive"))
      (node (ref "C6") (pin "1") (pinfunction "1_1") (pintype "passive"))
      (node (ref "R_BOOT") (pin "1") (pinfunction "1_1") (pintype "passive"))
      (node (ref "U2") (pin "15") (pinfunction "IO9_15") (pintype "bidirectional"))
    )
    (net (code "19") (name "IO{slash}CHANGE") (class "Default")
      (node (ref "C10") (pin "1") (pinfunction "1_1") (pintype "passive"))
      (node (ref "CHANGE_BUTTON") (pin "3") (pinfunction "3_3") (pintype "passive"))
      (node (ref "CHANGE_BUTTON") (pin "4") (pinfunction "4_4") (pintype "passive"))
      (node (ref "R_CHANGE") (pin "1") (pinfunction "1_1") (pintype "passive"))
      (node (ref "U2") (pin "23") (pinfunction "IO15_23") (pintype "bidirectional"))
    )
    (net (code "20") (name "MISO") (class "Default")
      (node (ref "D12") (pin "2") (pinfunction "2_2") (pintype "passive"))
      (node (ref "J4") (pin "P7") (pinfunction "DAT0_P7") (pintype "bidirectional"))
      (node (ref "R8") (pin "1") (pinfunction "1_1") (pintype "passive"))
      (node (ref "TP6") (pin "TP") (pinfunction "TP_TP") (pintype "input"))
      (node (ref "U1") (pin "2") (pinfunction "DO(IO1)_2") (pintype "bidirectional"))
      (node (ref "U2") (pin "27") (pinfunction "IO2_27") (pintype "bidirectional"))
    )
    (net (code "21") (name "MOSI") (class "Default")
      (node (ref "D11") (pin "2") (pinfunction "2_2") (pintype "passive"))
      (node (ref "J1") (pin "14") (pinfunction "14_14") (pintype "bidirectional"))
      (node (ref "J4") (pin "P3") (pinfunction "CMD_P3") (pintype "bidirectional"))
      (node (ref "R7") (pin "1") (pinfunction "1_1") (pintype "passive"))
      (node (ref "TP7") (pin "TP") (pinfunction "TP_TP") (pintype "input"))
      (node (ref "U1") (pin "5") (pinfunction "DI(IO0)_5") (pintype "bidirectional"))
      (node (ref "U2") (pin "7") (pinfunction "IO7_7") (pintype "bidirectional"))
    )
    (net (code "22") (name "Net-(D2-CATHODE)") (class "Default")
      (node (ref "C1_BAT1") (pin "1") (pinfunction "1_1") (pintype "passive"))
      (node (ref "D2") (pin "1") (pinfunction "CATHODE_1") (pintype "bidirectional"))
      (node (ref "IC4") (pin "1") (pinfunction "VIN_1") (pintype "bidirectional"))
      (node (ref "IC4") (pin "3") (pinfunction "CE_3") (pintype "bidirectional"))
      (node (ref "Q1") (pin "2") (pinfunction "S_2") (pintype "bidirectional"))
    )
    (net (code "23") (name "Net-(D7-CATHODE)") (class "Default")
      (node (ref "D7") (pin "1") (pinfunction "CATHODE_1") (pintype "bidirectional"))
      (node (ref "R_CAPACITOR") (pin "2") (pinfunction "2_2") (pintype "passive"))
    )
    (net (code "24") (name "Net-(EPD_C1-Pad1)") (class "Default")
      (node (ref "EPD_C1") (pin "1") (pinfunction "1_1") (pintype "passive"))
      (node (ref "J1") (pin "4") (pinfunction "4_4") (pintype "bidirectional"))
    )
    (net (code "25") (name "Net-(EPD_C2-Pad2)") (class "Default")
      (node (ref "EPD_C2") (pin "2") (pinfunction "2_2") (pintype "passive"))
      (node (ref "J1") (pin "5") (pinfunction "5_5") (pintype "bidirectional"))
    )
    (net (code "26") (name "Net-(EPD_C6-Pad1)") (class "Default")
      (node (ref "EPD_C6") (pin "1") (pinfunction "1_1") (pintype "passive"))
      (node (ref "J1") (pin "18") (pinfunction "18_18") (pintype "bidirectional"))
    )
    (net (code "27") (name "Net-(EPD_C7-Pad1)") (class "Default")
      (node (ref "EPD_C7") (pin "1") (pinfunction "1_1") (pintype "passive"))
      (node (ref "J1") (pin "19") (pinfunction "19_19") (pintype "bidirectional"))
    )
    (net (code "28") (name "Net-(EPD_C8-Pad1)") (class "Default")
      (node (ref "EPD_C8") (pin "1") (pinfunction "1_1") (pintype "passive"))
      (node (ref "J1") (pin "20") (pinfunction "20_20") (pintype "bidirectional"))
    )
    (net (code "29") (name "Net-(EPD_C10-Pad1)") (class "Default")
      (node (ref "EPD_C10") (pin "1") (pinfunction "1_1") (pintype "passive"))
      (node (ref "J1") (pin "22") (pinfunction "22_22") (pintype "bidirectional"))
    )
    (net (code "30") (name "Net-(EPD_C12-Pad1)") (class "Default")
      (node (ref "EPD_C12") (pin "1") (pinfunction "1_1") (pintype "passive"))
      (node (ref "J1") (pin "24") (pinfunction "24_24") (pintype "bidirectional"))
    )
    (net (code "31") (name "Net-(IC1-CT)") (class "Default")
      (node (ref "C_DELAY") (pin "1") (pinfunction "1_1") (pintype "passive"))
      (node (ref "IC1") (pin "5") (pinfunction "CT_5") (pintype "bidirectional"))
    )
    (net (code "32") (name "Net-(J2-PadA5)") (class "Default")
      (node (ref "J2") (pin "A5") (pinfunction "A5_A5") (pintype "bidirectional"))
      (node (ref "R2-USB1") (pin "2") (pinfunction "2_2") (pintype "passive"))
    )
    (net (code "33") (name "Net-(J2-PadB5)") (class "Default")
      (node (ref "J2") (pin "B5") (pinfunction "B5_B5") (pintype "bidirectional"))
      (node (ref "R2-USB") (pin "1") (pinfunction "1_1") (pintype "passive"))
    )
    (net (code "34") (name "Net-(MCP73831-PROG)") (class "Default")
      (node (ref "MCP73831") (pin "5") (pinfunction "PROG_5") (pintype "input"))
      (node (ref "R2_BAT") (pin "2") (pinfunction "2_2") (pintype "passive"))
    )
    (net (code "35") (name "PREVGH") (class "Default")
      (node (ref "D5") (pin "1") (pinfunction "K_1") (pintype "bidirectional"))
      (node (ref "EPD_C9") (pin "1") (pinfunction "1_1") (pintype "passive"))
      (node (ref "J1") (pin "21") (pinfunction "21_21") (pintype "bidirectional"))
    )
    (net (code "36") (name "PREVGL") (class "Default")
      (node (ref "D4") (pin "2") (pinfunction "A_2") (pintype "bidirectional"))
      (node (ref "EPD_C11") (pin "1") (pinfunction "1_1") (pintype "passive"))
      (node (ref "J1") (pin "23") (pinfunction "23_23") (pintype "bidirectional"))
    )
    (net (code "37") (name "RESE") (class "Default")
      (node (ref "J1") (pin "3") (pinfunction "3_3") (pintype "bidirectional"))
      (node (ref "Q3") (pin "2") (pinfunction "S_2") (pintype "bidirectional"))
      (node (ref "R3") (pin "2") (pinfunction "2_2") (pintype "passive"))
    )
    (net (code "38") (name "RESE'") (class "Default")
      (node (ref "R2") (pin "2") (pinfunction "2_2") (pintype "passive"))
      (node (ref "R3") (pin "1") (pinfunction "1_1") (pintype "passive"))
      (node (ref "SJ1") (pin "2") (pinfunction "2_2") (pintype "passive"))
    )
    (net (code "39") (name "RESET") (class "Default")
      (node (ref "C5") (pin "1") (pinfunction "1_1") (pintype "passive"))
      (node (ref "IC1") (pin "1") (pinfunction "VOUT_1") (pintype "bidirectional"))
      (node (ref "RESET_BUTTON") (pin "3") (pinfunction "3_3") (pintype "passive"))
      (node (ref "RESET_BUTTON") (pin "4") (pinfunction "4_4") (pintype "passive"))
      (node (ref "R_RESET") (pin "1") (pinfunction "1_1") (pintype "passive"))
      (node (ref "U2") (pin "3") (pinfunction "EN_3") (pintype "input"))
    )
    (net (code "40") (name "RTC_RST") (class "Default")
      (node (ref "U2") (pin "16") (pinfunction "IO18_16") (pintype "bidirectional"))
      (node (ref "U3") (pin "4") (pinfunction "~{RST}_4") (pintype "input"))
    )
    (net (code "41") (name "RX") (class "Default")
      (node (ref "TP2") (pin "TP") (pinfunction "TP_TP") (pintype "input"))
      (node (ref "U2") (pin "24") (pinfunction "RXD0/GPIO17_24") (pintype "bidirectional"))
    )
    (net (code "42") (name "SCK") (class "Default")
      (node (ref "D10") (pin "2") (pinfunction "2_2") (pintype "passive"))
      (node (ref "J1") (pin "13") (pinfunction "13_13") (pintype "bidirectional"))
      (node (ref "J4") (pin "P5") (pinfunction "CLK_P5") (pintype "bidirectional"))
      (node (ref "R6") (pin "1") (pinfunction "1_1") (pintype "passive"))
      (node (ref "TP8") (pin "TP") (pinfunction "TP_TP") (pintype "input"))
      (node (ref "U1") (pin "6") (pinfunction "CLK_6") (pintype "input"))
      (node (ref "U2") (pin "6") (pinfunction "IO6_6") (pintype "bidirectional"))
    )
    (net (code "43") (name "SCL") (class "Default")
      (node (ref "J3") (pin "4") (pinfunction "4_4") (pintype "passive"))
      (node (ref "R2-PINH") (pin "1") (pinfunction "1_1") (pintype "passive"))
      (node (ref "SENSOR2") (pin "4") (pinfunction "SCK_4") (pintype "input"))
      (node (ref "U2") (pin "20") (pinfunction "IO22_20") (pintype "bidirectional"))
      (node (ref "U3") (pin "16") (pinfunction "SCL_16") (pintype "input"))
      (node (ref "U4") (pin "7") (pinfunction "SCL_7") (pintype "input"))
    )
    (net (code "44") (name "SDA") (class "Default")
      (node (ref "J3") (pin "3") (pinfunction "3_3") (pintype "passive"))
      (node (ref "R1_PINH") (pin "1") (pinfunction "1_1") (pintype "passive"))
      (node (ref "SENSOR2") (pin "3") (pinfunction "SDI_3") (pintype "bidirectional"))
      (node (ref "U2") (pin "19") (pinfunction "IO21_19") (pintype "bidirectional"))
      (node (ref "U3") (pin "15") (pinfunction "SDA_15") (pintype "bidirectional"))
      (node (ref "U4") (pin "8") (pinfunction "SDA_8") (pintype "bidirectional"))
    )
    (net (code "45") (name "SRC") (class "Default")
      (node (ref "C4") (pin "1") (pinfunction "1_1") (pintype "passive"))
      (node (ref "C4") (pin "2") (pinfunction "2_2") (pintype "passive"))
      (node (ref "D3") (pin "2") (pinfunction "A_2") (pintype "bidirectional"))
      (node (ref "D4") (pin "1") (pinfunction "K_1") (pintype "bidirectional"))
      (node (ref "D5") (pin "2") (pinfunction "A_2") (pintype "bidirectional"))
      (node (ref "L1") (pin "1") (pinfunction "1_1") (pintype "passive"))
      (node (ref "Q3") (pin "3") (pinfunction "D_3") (pintype "bidirectional"))
    )
    (net (code "46") (name "SS_SD") (class "Default")
      (node (ref "D8") (pin "2") (pinfunction "2_2") (pintype "passive"))
      (node (ref "J4") (pin "P2") (pinfunction "CD/DAT3_P2") (pintype "bidirectional"))
      (node (ref "R10") (pin "1") (pinfunction "1_1") (pintype "passive"))
      (node (ref "U2") (pin "4") (pinfunction "IO4_4") (pintype "bidirectional"))
    )
    (net (code "47") (name "TX") (class "Default")
      (node (ref "TP1") (pin "TP") (pinfunction "TP_TP") (pintype "input"))
      (node (ref "U2") (pin "25") (pinfunction "TXD0/GPIO16_25") (pintype "bidirectional"))
    )
    (net (code "48") (name "USB_D+") (class "Default")
      (node (ref "D1") (pin "1") (pinfunction "I/O1_1_1") (pintype "bidirectional"))
      (node (ref "U2") (pin "14") (pinfunction "IO13_14") (pintype "bidirectional"))
    )
    (net (code "49") (name "USB_D-") (class "Default")
      (node (ref "D1") (pin "3") (pinfunction "I/O2_1_3") (pintype "bidirectional"))
      (node (ref "U2") (pin "13") (pinfunction "IO12_13") (pintype "bidirectional"))
    )
    (net (code "50") (name "VBAT") (class "Default")
      (node (ref "C2_BAT") (pin "1") (pinfunction "1_1") (pintype "passive"))
      (node (ref "MCP73831") (pin "3") (pinfunction "VBAT_3") (pintype "power_in"))
      (node (ref "Q1") (pin "3") (pinfunction "D_3") (pintype "bidirectional"))
      (node (ref "TP3") (pin "TP") (pinfunction "TP_TP") (pintype "input"))
      (node (ref "U4") (pin "2") (pinfunction "CELL_2") (pintype "power_in"))
      (node (ref "U4") (pin "3") (pinfunction "VDD_3") (pintype "power_in"))
    )
    (net (code "51") (name "VBUS") (class "Default")
      (node (ref "C1_BAT") (pin "1") (pinfunction "1_1") (pintype "passive"))
      (node (ref "C4_USB") (pin "1") (pinfunction "1_1") (pintype "passive"))
      (node (ref "C5_USB") (pin "1") (pinfunction "1_1") (pintype "passive"))
      (node (ref "CHG_LED") (pin "A") (pinfunction "A_A") (pintype "passive"))
      (node (ref "D1") (pin "5") (pinfunction "VBUS_5") (pintype "bidirectional"))
      (node (ref "D2") (pin "2") (pinfunction "ANODE_2") (pintype "bidirectional"))
      (node (ref "MCP73831") (pin "4") (pinfunction "VIN_4") (pintype "power_in"))
      (node (ref "PFMF.050.1") (pin "2") (pinfunction "2_2") (pintype "passive"))
      (node (ref "Q1") (pin "1") (pinfunction "G_1") (pintype "bidirectional"))
      (node (ref "R1_PWRUSB") (pin "2") (pinfunction "2_2") (pintype "passive"))
      (node (ref "TP14") (pin "TP") (pinfunction "TP_TP") (pintype "input"))
    )
    (net (code "52") (name "VRTC") (class "Default")
      (node (ref "C10_SUPERCAP") (pin "2") (pinfunction "2_2") (pintype "passive"))
      (node (ref "C8") (pin "1") (pinfunction "1_1") (pintype "passive"))
      (node (ref "R_CAPACITOR") (pin "1") (pinfunction "1_1") (pintype "passive"))
      (node (ref "U3") (pin "14") (pinfunction "VBAT_14") (pintype "power_in"))
    )
    (net (code "53") (name "VUSB") (class "Default")
      (node (ref "J2") (pin "A4") (pinfunction "A4_A4") (pintype "bidirectional"))
      (node (ref "J2") (pin "A9") (pinfunction "A9_A9") (pintype "bidirectional"))
      (node (ref "J2") (pin "B4") (pinfunction "B4_B4") (pintype "bidirectional"))
      (node (ref "J2") (pin "B9") (pinfunction "B9_B9") (pintype "bidirectional"))
      (node (ref "PFMF.050.1") (pin "1") (pinfunction "1_1") (pintype "passive"))
    )
    (net (code "54") (name "unconnected-(IC1-NC-Pad4)") (class "Default")
      (node (ref "IC1") (pin "4") (pinfunction "NC_4") (pintype "no_connect"))
    )
    (net (code "55") (name "unconnected-(IC4-NC-Pad4)") (class "Default")
      (node (ref "IC4") (pin "4") (pinfunction "NC_4") (pintype "no_connect"))
    )
    (net (code "56") (name "unconnected-(J1-Pad1)") (class "Default")
      (node (ref "J1") (pin "1") (pinfunction "1_1") (pintype "bidirectional"))
    )
    (net (code "57") (name "unconnected-(J1-Pad6)") (class "Default")
      (node (ref "J1") (pin "6") (pinfunction "6_6") (pintype "bidirectional"))
    )
    (net (code "58") (name "unconnected-(J1-Pad7)") (class "Default")
      (node (ref "J1") (pin "7") (pinfunction "7_7") (pintype "bidirectional"))
    )
    (net (code "59") (name "unconnected-(J2-PadA8)") (class "Default")
      (node (ref "J2") (pin "A8") (pinfunction "A8_A8") (pintype "bidirectional"))
    )
    (net (code "60") (name "unconnected-(J2-PadB8)") (class "Default")
      (node (ref "J2") (pin "B8") (pinfunction "B8_B8") (pintype "bidirectional"))
    )
    (net (code "61") (name "unconnected-(J4-DAT1-PadP8)") (class "Default")
      (node (ref "J4") (pin "P8") (pinfunction "DAT1_P8") (pintype "bidirectional"))
    )
    (net (code "62") (name "unconnected-(J4-DAT2-PadP1)") (class "Default")
      (node (ref "J4") (pin "P1") (pinfunction "DAT2_P1") (pintype "bidirectional"))
    )
    (net (code "63") (name "unconnected-(J4-DETECTION_1-PadS1)") (class "Default")
      (node (ref "J4") (pin "S1") (pinfunction "DETECTION_1_S1") (pintype "bidirectional"))
    )
    (net (code "64") (name "unconnected-(J4-DETECTION_2-PadS2)") (class "Default")
      (node (ref "J4") (pin "S2") (pinfunction "DETECTION_2_S2") (pintype "bidirectional"))
    )
    (net (code "65") (name "unconnected-(U2-NC-Pad22)") (class "Default")
      (node (ref "U2") (pin "22") (pinfunction "NC_22") (pintype "no_connect"))
    )
    (net (code "66") (name "unconnected-(U4-~{ALERT}-Pad5)") (class "Default")
      (node (ref "U4") (pin "5") (pinfunction "~{ALERT}_5") (pintype "output"))
    )
  )
)
